# keep-it-lit.net
KiCad netlist of a schematic drawn in EAGLE
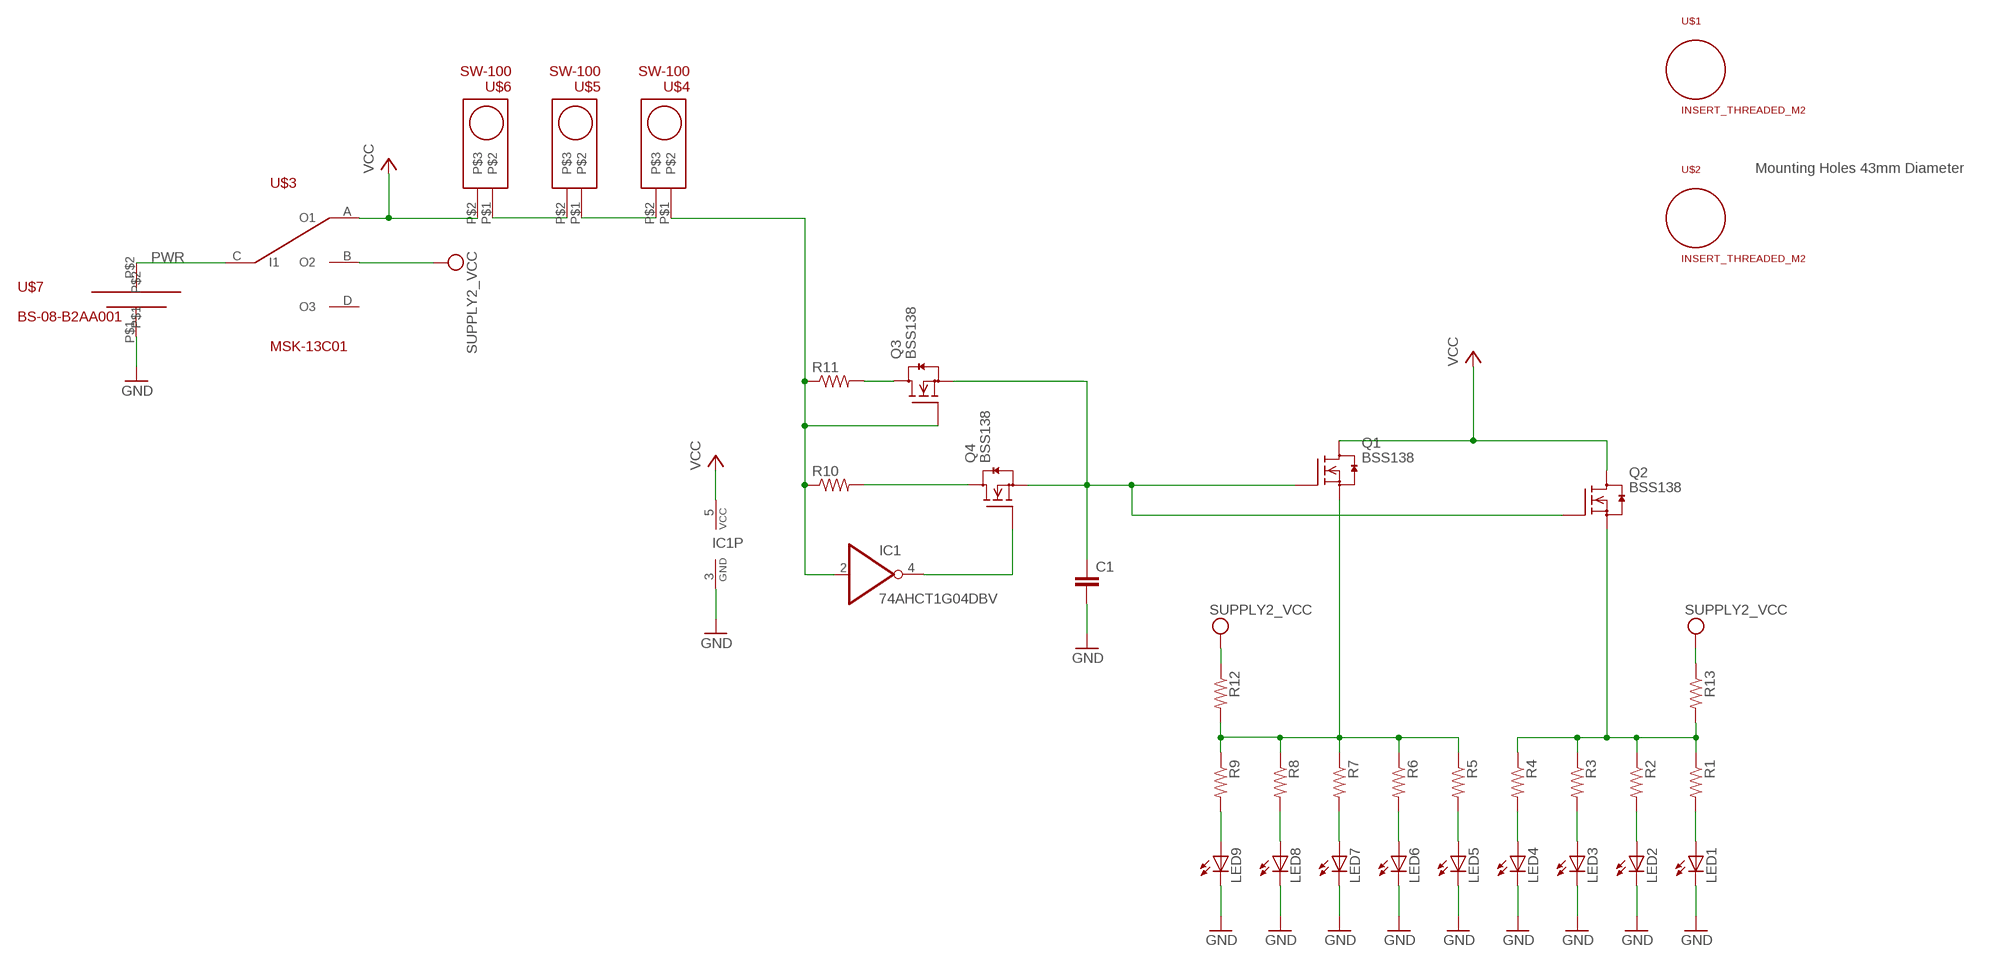
[diagram p0: schematic, sheet 1]

(export (version "E")
  (design (tool "Eeschema 10.0.6"))
  (components
    (comp (ref "C1")
      (value "CAP0603-CAP")
      (footprint "eagle-import:0603-CAP")
      (libsource (lib "eagle-import") (part "CAP0603-CAP"))
    )
    (comp (ref "IC1")
      (value "74AHCT1G04DBV")
      (footprint "eagle-import:SOT23-5")
      (libsource (lib "eagle-import") (part "741G04DBVAHCT"))
    )
    (comp (ref "LED1")
      (value "LEDCHIPLED_1206")
      (footprint "eagle-import:CHIPLED_1206")
      (libsource (lib "eagle-import") (part "LEDCHIPLED_1206"))
    )
    (comp (ref "LED2")
      (value "LEDCHIPLED_1206")
      (footprint "eagle-import:CHIPLED_1206")
      (libsource (lib "eagle-import") (part "LEDCHIPLED_1206"))
    )
    (comp (ref "LED3")
      (value "LEDCHIPLED_1206")
      (footprint "eagle-import:CHIPLED_1206")
      (libsource (lib "eagle-import") (part "LEDCHIPLED_1206"))
    )
    (comp (ref "LED4")
      (value "LEDCHIPLED_1206")
      (footprint "eagle-import:CHIPLED_1206")
      (libsource (lib "eagle-import") (part "LEDCHIPLED_1206"))
    )
    (comp (ref "LED5")
      (value "LEDCHIPLED_1206")
      (footprint "eagle-import:CHIPLED_1206")
      (libsource (lib "eagle-import") (part "LEDCHIPLED_1206"))
    )
    (comp (ref "LED6")
      (value "LEDCHIPLED_1206")
      (footprint "eagle-import:CHIPLED_1206")
      (libsource (lib "eagle-import") (part "LEDCHIPLED_1206"))
    )
    (comp (ref "LED7")
      (value "LEDCHIPLED_1206")
      (footprint "eagle-import:CHIPLED_1206")
      (libsource (lib "eagle-import") (part "LEDCHIPLED_1206"))
    )
    (comp (ref "LED8")
      (value "LEDCHIPLED_1206")
      (footprint "eagle-import:CHIPLED_1206")
      (libsource (lib "eagle-import") (part "LEDCHIPLED_1206"))
    )
    (comp (ref "LED9")
      (value "LEDCHIPLED_1206")
      (footprint "eagle-import:CHIPLED_1206")
      (libsource (lib "eagle-import") (part "LEDCHIPLED_1206"))
    )
    (comp (ref "Q1")
      (value "BSS138")
      (footprint "eagle-import:SOT23")
      (libsource (lib "eagle-import") (part "BSS138"))
    )
    (comp (ref "Q2")
      (value "BSS138")
      (footprint "eagle-import:SOT23")
      (libsource (lib "eagle-import") (part "BSS138"))
    )
    (comp (ref "Q3")
      (value "BSS138")
      (footprint "eagle-import:SOT23")
      (libsource (lib "eagle-import") (part "BSS138"))
    )
    (comp (ref "Q4")
      (value "BSS138")
      (footprint "eagle-import:SOT23")
      (libsource (lib "eagle-import") (part "BSS138"))
    )
    (comp (ref "R1")
      (value "RESISTOR0603-RES")
      (footprint "eagle-import:0603-RES")
      (libsource (lib "eagle-import") (part "RESISTOR0603-RES"))
    )
    (comp (ref "R2")
      (value "RESISTOR0603-RES")
      (footprint "eagle-import:0603-RES")
      (libsource (lib "eagle-import") (part "RESISTOR0603-RES"))
    )
    (comp (ref "R3")
      (value "RESISTOR0603-RES")
      (footprint "eagle-import:0603-RES")
      (libsource (lib "eagle-import") (part "RESISTOR0603-RES"))
    )
    (comp (ref "R4")
      (value "RESISTOR0603-RES")
      (footprint "eagle-import:0603-RES")
      (libsource (lib "eagle-import") (part "RESISTOR0603-RES"))
    )
    (comp (ref "R5")
      (value "RESISTOR0603-RES")
      (footprint "eagle-import:0603-RES")
      (libsource (lib "eagle-import") (part "RESISTOR0603-RES"))
    )
    (comp (ref "R6")
      (value "RESISTOR0603-RES")
      (footprint "eagle-import:0603-RES")
      (libsource (lib "eagle-import") (part "RESISTOR0603-RES"))
    )
    (comp (ref "R7")
      (value "RESISTOR0603-RES")
      (footprint "eagle-import:0603-RES")
      (libsource (lib "eagle-import") (part "RESISTOR0603-RES"))
    )
    (comp (ref "R8")
      (value "RESISTOR0603-RES")
      (footprint "eagle-import:0603-RES")
      (libsource (lib "eagle-import") (part "RESISTOR0603-RES"))
    )
    (comp (ref "R9")
      (value "RESISTOR0603-RES")
      (footprint "eagle-import:0603-RES")
      (libsource (lib "eagle-import") (part "RESISTOR0603-RES"))
    )
    (comp (ref "R10")
      (value "RESISTOR0603-RES")
      (footprint "eagle-import:0603-RES")
      (libsource (lib "eagle-import") (part "RESISTOR0603-RES"))
    )
    (comp (ref "R11")
      (value "RESISTOR0603-RES")
      (footprint "eagle-import:0603-RES")
      (libsource (lib "eagle-import") (part "RESISTOR0603-RES"))
    )
    (comp (ref "R12")
      (value "RESISTOR0603-RES")
      (footprint "eagle-import:0603-RES")
      (libsource (lib "eagle-import") (part "RESISTOR0603-RES"))
    )
    (comp (ref "R13")
      (value "RESISTOR0603-RES")
      (footprint "eagle-import:0603-RES")
      (libsource (lib "eagle-import") (part "RESISTOR0603-RES"))
    )
    (comp (ref "U$1")
      (value "INSERT_THREADED_M2")
      (footprint "eagle-import:INSERT_M2")
      (libsource (lib "eagle-import") (part "INSERT_THREADED_M2"))
    )
    (comp (ref "U$2")
      (value "INSERT_THREADED_M2")
      (footprint "eagle-import:INSERT_M2")
      (libsource (lib "eagle-import") (part "INSERT_THREADED_M2"))
    )
    (comp (ref "U$3")
      (value "MSK-13C01")
      (footprint "eagle-import:SWITCH_SP3T")
      (libsource (lib "eagle-import") (part "MSK-13C01"))
    )
    (comp (ref "U$4")
      (value "SW-100")
      (footprint "eagle-import:SWITCH_TILT")
      (libsource (lib "eagle-import") (part "SW-100"))
    )
    (comp (ref "U$5")
      (value "SW-100")
      (footprint "eagle-import:SWITCH_TILT")
      (libsource (lib "eagle-import") (part "SW-100"))
    )
    (comp (ref "U$6")
      (value "SW-100")
      (footprint "eagle-import:SWITCH_TILT")
      (libsource (lib "eagle-import") (part "SW-100"))
    )
    (comp (ref "U$7")
      (value "BS-08-B2AA001")
      (footprint "eagle-import:BATTERY_CONNECTOR_CR2032")
      (libsource (lib "eagle-import") (part "BS-08-B2AA001"))
    )
  )
  (nets
    (net (code "1") (name "/PWR") (class "Default")
      (node (ref "U$3") (pin "C") (pinfunction "I1_C") (pintype "bidirectional"))
      (node (ref "U$7") (pin "P$2") (pinfunction "P$1_P$2") (pintype "bidirectional"))
    )
    (net (code "2") (name "GND") (class "Default")
      (node (ref "C1") (pin "2") (pinfunction "2_2") (pintype "passive"))
      (node (ref "IC1") (pin "3") (pinfunction "GND_3") (pintype "power_in"))
      (node (ref "LED1") (pin "C") (pinfunction "C_C") (pintype "passive"))
      (node (ref "LED2") (pin "C") (pinfunction "C_C") (pintype "passive"))
      (node (ref "LED3") (pin "C") (pinfunction "C_C") (pintype "passive"))
      (node (ref "LED4") (pin "C") (pinfunction "C_C") (pintype "passive"))
      (node (ref "LED5") (pin "C") (pinfunction "C_C") (pintype "passive"))
      (node (ref "LED6") (pin "C") (pinfunction "C_C") (pintype "passive"))
      (node (ref "LED7") (pin "C") (pinfunction "C_C") (pintype "passive"))
      (node (ref "LED8") (pin "C") (pinfunction "C_C") (pintype "passive"))
      (node (ref "LED9") (pin "C") (pinfunction "C_C") (pintype "passive"))
      (node (ref "U$7") (pin "P$1") (pinfunction "P$2_P$1") (pintype "bidirectional"))
    )
    (net (code "3") (name "Net-(IC1A-I)") (class "Default")
      (node (ref "IC1") (pin "2") (pinfunction "I_2") (pintype "input"))
      (node (ref "Q3") (pin "1") (pinfunction "G_1") (pintype "passive"))
      (node (ref "R10") (pin "1") (pinfunction "1_1") (pintype "passive"))
      (node (ref "R11") (pin "1") (pinfunction "1_1") (pintype "passive"))
      (node (ref "U$4") (pin "P$1") (pinfunction "P$2_P$1") (pintype "bidirectional"))
    )
    (net (code "4") (name "Net-(IC1A-O)") (class "Default")
      (node (ref "IC1") (pin "4") (pinfunction "O_4") (pintype "output"))
      (node (ref "Q4") (pin "1") (pinfunction "G_1") (pintype "passive"))
    )
    (net (code "5") (name "Net-(LED1-PadA)") (class "Default")
      (node (ref "LED1") (pin "A") (pinfunction "A_A") (pintype "passive"))
      (node (ref "R1") (pin "2") (pinfunction "2_2") (pintype "passive"))
    )
    (net (code "6") (name "Net-(LED2-PadA)") (class "Default")
      (node (ref "LED2") (pin "A") (pinfunction "A_A") (pintype "passive"))
      (node (ref "R2") (pin "2") (pinfunction "2_2") (pintype "passive"))
    )
    (net (code "7") (name "Net-(LED3-PadA)") (class "Default")
      (node (ref "LED3") (pin "A") (pinfunction "A_A") (pintype "passive"))
      (node (ref "R3") (pin "2") (pinfunction "2_2") (pintype "passive"))
    )
    (net (code "8") (name "Net-(LED4-PadA)") (class "Default")
      (node (ref "LED4") (pin "A") (pinfunction "A_A") (pintype "passive"))
      (node (ref "R4") (pin "2") (pinfunction "2_2") (pintype "passive"))
    )
    (net (code "9") (name "Net-(LED5-PadA)") (class "Default")
      (node (ref "LED5") (pin "A") (pinfunction "A_A") (pintype "passive"))
      (node (ref "R5") (pin "2") (pinfunction "2_2") (pintype "passive"))
    )
    (net (code "10") (name "Net-(LED6-PadA)") (class "Default")
      (node (ref "LED6") (pin "A") (pinfunction "A_A") (pintype "passive"))
      (node (ref "R6") (pin "2") (pinfunction "2_2") (pintype "passive"))
    )
    (net (code "11") (name "Net-(LED7-PadA)") (class "Default")
      (node (ref "LED7") (pin "A") (pinfunction "A_A") (pintype "passive"))
      (node (ref "R7") (pin "2") (pinfunction "2_2") (pintype "passive"))
    )
    (net (code "12") (name "Net-(LED8-PadA)") (class "Default")
      (node (ref "LED8") (pin "A") (pinfunction "A_A") (pintype "passive"))
      (node (ref "R8") (pin "2") (pinfunction "2_2") (pintype "passive"))
    )
    (net (code "13") (name "Net-(LED9-PadA)") (class "Default")
      (node (ref "LED9") (pin "A") (pinfunction "A_A") (pintype "passive"))
      (node (ref "R9") (pin "2") (pinfunction "2_2") (pintype "passive"))
    )
    (net (code "14") (name "Net-(Q1-G)") (class "Default")
      (node (ref "C1") (pin "1") (pinfunction "1_1") (pintype "passive"))
      (node (ref "Q1") (pin "1") (pinfunction "G_1") (pintype "passive"))
      (node (ref "Q2") (pin "1") (pinfunction "G_1") (pintype "passive"))
      (node (ref "Q3") (pin "2") (pinfunction "S_2") (pintype "passive"))
      (node (ref "Q4") (pin "2") (pinfunction "S_2") (pintype "passive"))
    )
    (net (code "15") (name "Net-(Q1-S)") (class "Default")
      (node (ref "Q1") (pin "2") (pinfunction "S_2") (pintype "passive"))
      (node (ref "R12") (pin "2") (pinfunction "2_2") (pintype "passive"))
      (node (ref "R5") (pin "1") (pinfunction "1_1") (pintype "passive"))
      (node (ref "R6") (pin "1") (pinfunction "1_1") (pintype "passive"))
      (node (ref "R7") (pin "1") (pinfunction "1_1") (pintype "passive"))
      (node (ref "R8") (pin "1") (pinfunction "1_1") (pintype "passive"))
      (node (ref "R9") (pin "1") (pinfunction "1_1") (pintype "passive"))
    )
    (net (code "16") (name "Net-(Q2-S)") (class "Default")
      (node (ref "Q2") (pin "2") (pinfunction "S_2") (pintype "passive"))
      (node (ref "R1") (pin "1") (pinfunction "1_1") (pintype "passive"))
      (node (ref "R13") (pin "2") (pinfunction "2_2") (pintype "passive"))
      (node (ref "R2") (pin "1") (pinfunction "1_1") (pintype "passive"))
      (node (ref "R3") (pin "1") (pinfunction "1_1") (pintype "passive"))
      (node (ref "R4") (pin "1") (pinfunction "1_1") (pintype "passive"))
    )
    (net (code "17") (name "Net-(Q3-D)") (class "Default")
      (node (ref "Q3") (pin "3") (pinfunction "D_3") (pintype "passive"))
      (node (ref "R11") (pin "2") (pinfunction "2_2") (pintype "passive"))
    )
    (net (code "18") (name "Net-(Q4-D)") (class "Default")
      (node (ref "Q4") (pin "3") (pinfunction "D_3") (pintype "passive"))
      (node (ref "R10") (pin "2") (pinfunction "2_2") (pintype "passive"))
    )
    (net (code "19") (name "Net-(U$4-P$3)") (class "Default")
      (node (ref "U$4") (pin "P$2") (pinfunction "P$3_P$2") (pintype "bidirectional"))
      (node (ref "U$5") (pin "P$1") (pinfunction "P$2_P$1") (pintype "bidirectional"))
    )
    (net (code "20") (name "Net-(U$5-P$3)") (class "Default")
      (node (ref "U$5") (pin "P$2") (pinfunction "P$3_P$2") (pintype "bidirectional"))
      (node (ref "U$6") (pin "P$1") (pinfunction "P$2_P$1") (pintype "bidirectional"))
    )
    (net (code "21") (name "SUPPLY2_VCC") (class "Default")
      (node (ref "R12") (pin "1") (pinfunction "1_1") (pintype "passive"))
      (node (ref "R13") (pin "1") (pinfunction "1_1") (pintype "passive"))
      (node (ref "U$3") (pin "B") (pinfunction "O2_B") (pintype "bidirectional"))
    )
    (net (code "22") (name "VCC") (class "Default")
      (node (ref "IC1") (pin "5") (pinfunction "VCC_5") (pintype "power_in"))
      (node (ref "Q1") (pin "3") (pinfunction "D_3") (pintype "passive"))
      (node (ref "Q2") (pin "3") (pinfunction "D_3") (pintype "passive"))
      (node (ref "U$3") (pin "A") (pinfunction "O1_A") (pintype "bidirectional"))
      (node (ref "U$6") (pin "P$2") (pinfunction "P$3_P$2") (pintype "bidirectional"))
    )
    (net (code "23") (name "unconnected-(U$3-O3-PadD)") (class "Default")
      (node (ref "U$3") (pin "D") (pinfunction "O3_D") (pintype "bidirectional"))
    )
  )
)
